# LNA.net
KiCad netlist of a schematic drawn in Altium Designer
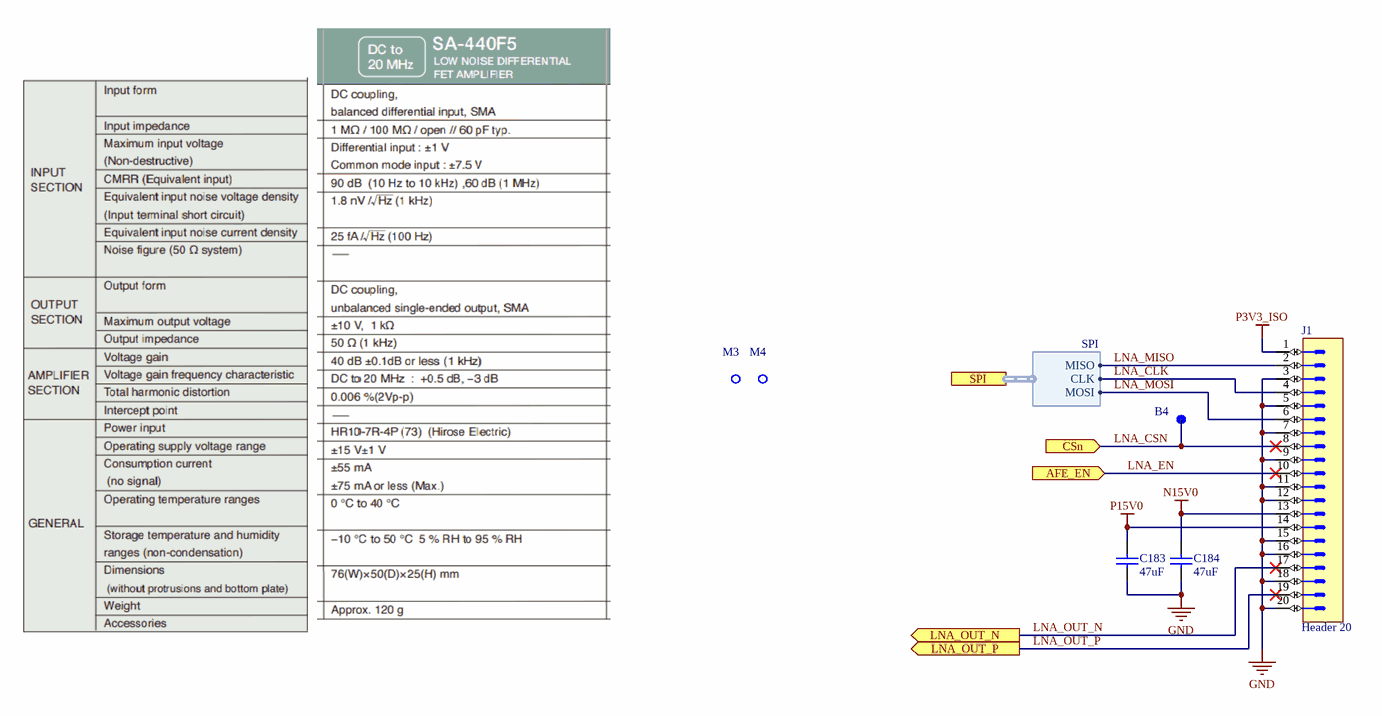
[diagram p0: LNA.SchDoc]

(export (version "E")
  (design (tool "Eeschema 10.0.6"))
  (components
    (comp (ref "B4")
      (value "SMD Pad")
      (footprint "C100")
      (description "Pad")
      (fields (field (name "PART NUMBER") "SMD_PAD_D1MM") (field (name "AUTHOR") "CERN DEM JLC"))
      (libsource (lib "Eletro-mechanical") (part "Single SMD Pad (Round)"))
    )
    (comp (ref "C183")
      (value "47uF")
      (footprint "CAPC3216X180N")
      (description "Non-polarised capacitor")
      (fields
        (field (name "PART NUMBER") "CC1206_47UF_25V_20%_X5R")
        (field (name "VOLTAGE") "25V")
        (field (name "AUTHOR") "CERN DEM JLC")
      )
      (libsource (lib "Capacitors") (part "Capacitor - non polarized"))
    )
    (comp (ref "C184")
      (value "47uF")
      (footprint "CAPC3216X180N")
      (description "Non-polarised capacitor")
      (fields
        (field (name "PART NUMBER") "CC1206_47UF_25V_20%_X5R")
        (field (name "VOLTAGE") "25V")
        (field (name "AUTHOR") "CERN DEM JLC")
      )
      (libsource (lib "Capacitors") (part "Capacitor - non polarized"))
    )
    (comp (ref "J1")
      (value "Header 20")
      (footprint "SAMTEC_HTSW-110-23-L-D")
      (description "Connector 20 Male")
      (fields
        (field (name "PART NUMBER") "SAMTEC_HTSW-110-23-L-D")
        (field (name "MANUFACTURER") "SAMTEC")
        (field (name "AUTHOR") "CERN DEM JLC")
      )
      (libsource (lib "Connectors") (part "Connector 20 Male"))
    )
    (comp (ref "M3")
      (value "Plated Hole")
      (footprint "MTG300_600")
      (description "Single Terminal Socket")
      (fields (field (name "PART NUMBER") "PLATED_HOLE3.0_PAD6.0") (field (name "AUTHOR") "CERN DEM JLC"))
      (libsource (lib "Eletro-mechanical") (part "Single Terminal Socket"))
    )
    (comp (ref "M4")
      (value "Plated Hole")
      (footprint "MTG300_600")
      (description "Single Terminal Socket")
      (fields (field (name "PART NUMBER") "PLATED_HOLE3.0_PAD6.0") (field (name "AUTHOR") "CERN DEM JLC"))
      (libsource (lib "Eletro-mechanical") (part "Single Terminal Socket"))
    )
  )
  (nets
    (net (code "2") (name "/LNA_CLK") (class "Default")
      (node (ref "J1") (pin "4") (pinfunction "4_4") (pintype "bidirectional"))
    )
    (net (code "3") (name "/LNA_CSN") (class "Default")
      (node (ref "B4") (pin "1") (pinfunction "1_1") (pintype "bidirectional"))
      (node (ref "J1") (pin "8") (pinfunction "8_8") (pintype "bidirectional"))
    )
    (net (code "4") (name "/LNA_EN") (class "Default")
      (node (ref "J1") (pin "10") (pinfunction "10_10") (pintype "bidirectional+no_connect"))
    )
    (net (code "5") (name "/LNA_MISO") (class "Default")
      (node (ref "J1") (pin "2") (pinfunction "2_2") (pintype "bidirectional"))
    )
    (net (code "6") (name "/LNA_MOSI") (class "Default")
      (node (ref "J1") (pin "6") (pinfunction "6_6") (pintype "bidirectional"))
    )
    (net (code "7") (name "/LNA_OUT_N") (class "Default")
      (node (ref "J1") (pin "17") (pinfunction "17_17") (pintype "bidirectional+no_connect"))
    )
    (net (code "8") (name "/LNA_OUT_P") (class "Default")
      (node (ref "J1") (pin "19") (pinfunction "19_19") (pintype "bidirectional+no_connect"))
    )
    (net (code "10") (name "GND") (class "Default")
      (node (ref "C183") (pin "2") (pinfunction "2_2") (pintype "passive"))
      (node (ref "C184") (pin "2") (pinfunction "2_2") (pintype "passive"))
      (node (ref "J1") (pin "11") (pinfunction "11_11") (pintype "bidirectional"))
      (node (ref "J1") (pin "12") (pinfunction "12_12") (pintype "bidirectional"))
      (node (ref "J1") (pin "15") (pinfunction "15_15") (pintype "bidirectional"))
      (node (ref "J1") (pin "16") (pinfunction "16_16") (pintype "bidirectional"))
      (node (ref "J1") (pin "18") (pinfunction "18_18") (pintype "bidirectional"))
      (node (ref "J1") (pin "20") (pinfunction "20_20") (pintype "bidirectional"))
      (node (ref "J1") (pin "3") (pinfunction "3_3") (pintype "bidirectional"))
      (node (ref "J1") (pin "5") (pinfunction "5_5") (pintype "bidirectional"))
      (node (ref "J1") (pin "7") (pinfunction "7_7") (pintype "bidirectional"))
      (node (ref "J1") (pin "9") (pinfunction "9_9") (pintype "bidirectional"))
    )
    (net (code "11") (name "N15V0") (class "Default")
      (node (ref "C184") (pin "1") (pinfunction "1_1") (pintype "passive"))
      (node (ref "J1") (pin "13") (pinfunction "13_13") (pintype "bidirectional"))
    )
    (net (code "12") (name "P3V3_ISO") (class "Default")
      (node (ref "J1") (pin "1") (pinfunction "1_1") (pintype "bidirectional"))
    )
    (net (code "13") (name "P15V0") (class "Default")
      (node (ref "C183") (pin "1") (pinfunction "1_1") (pintype "passive"))
      (node (ref "J1") (pin "14") (pinfunction "14_14") (pintype "bidirectional"))
    )
    (net (code "14") (name "unconnected-(M3-Pad1)") (class "Default")
      (node (ref "M3") (pin "1") (pinfunction "1_1") (pintype "bidirectional"))
    )
    (net (code "15") (name "unconnected-(M4-Pad1)") (class "Default")
      (node (ref "M4") (pin "1") (pinfunction "1_1") (pintype "bidirectional"))
    )
  )
)
